# BMS_Enerdel_Adapter_rev8.net
KiCad netlist of a schematic drawn in EAGLE
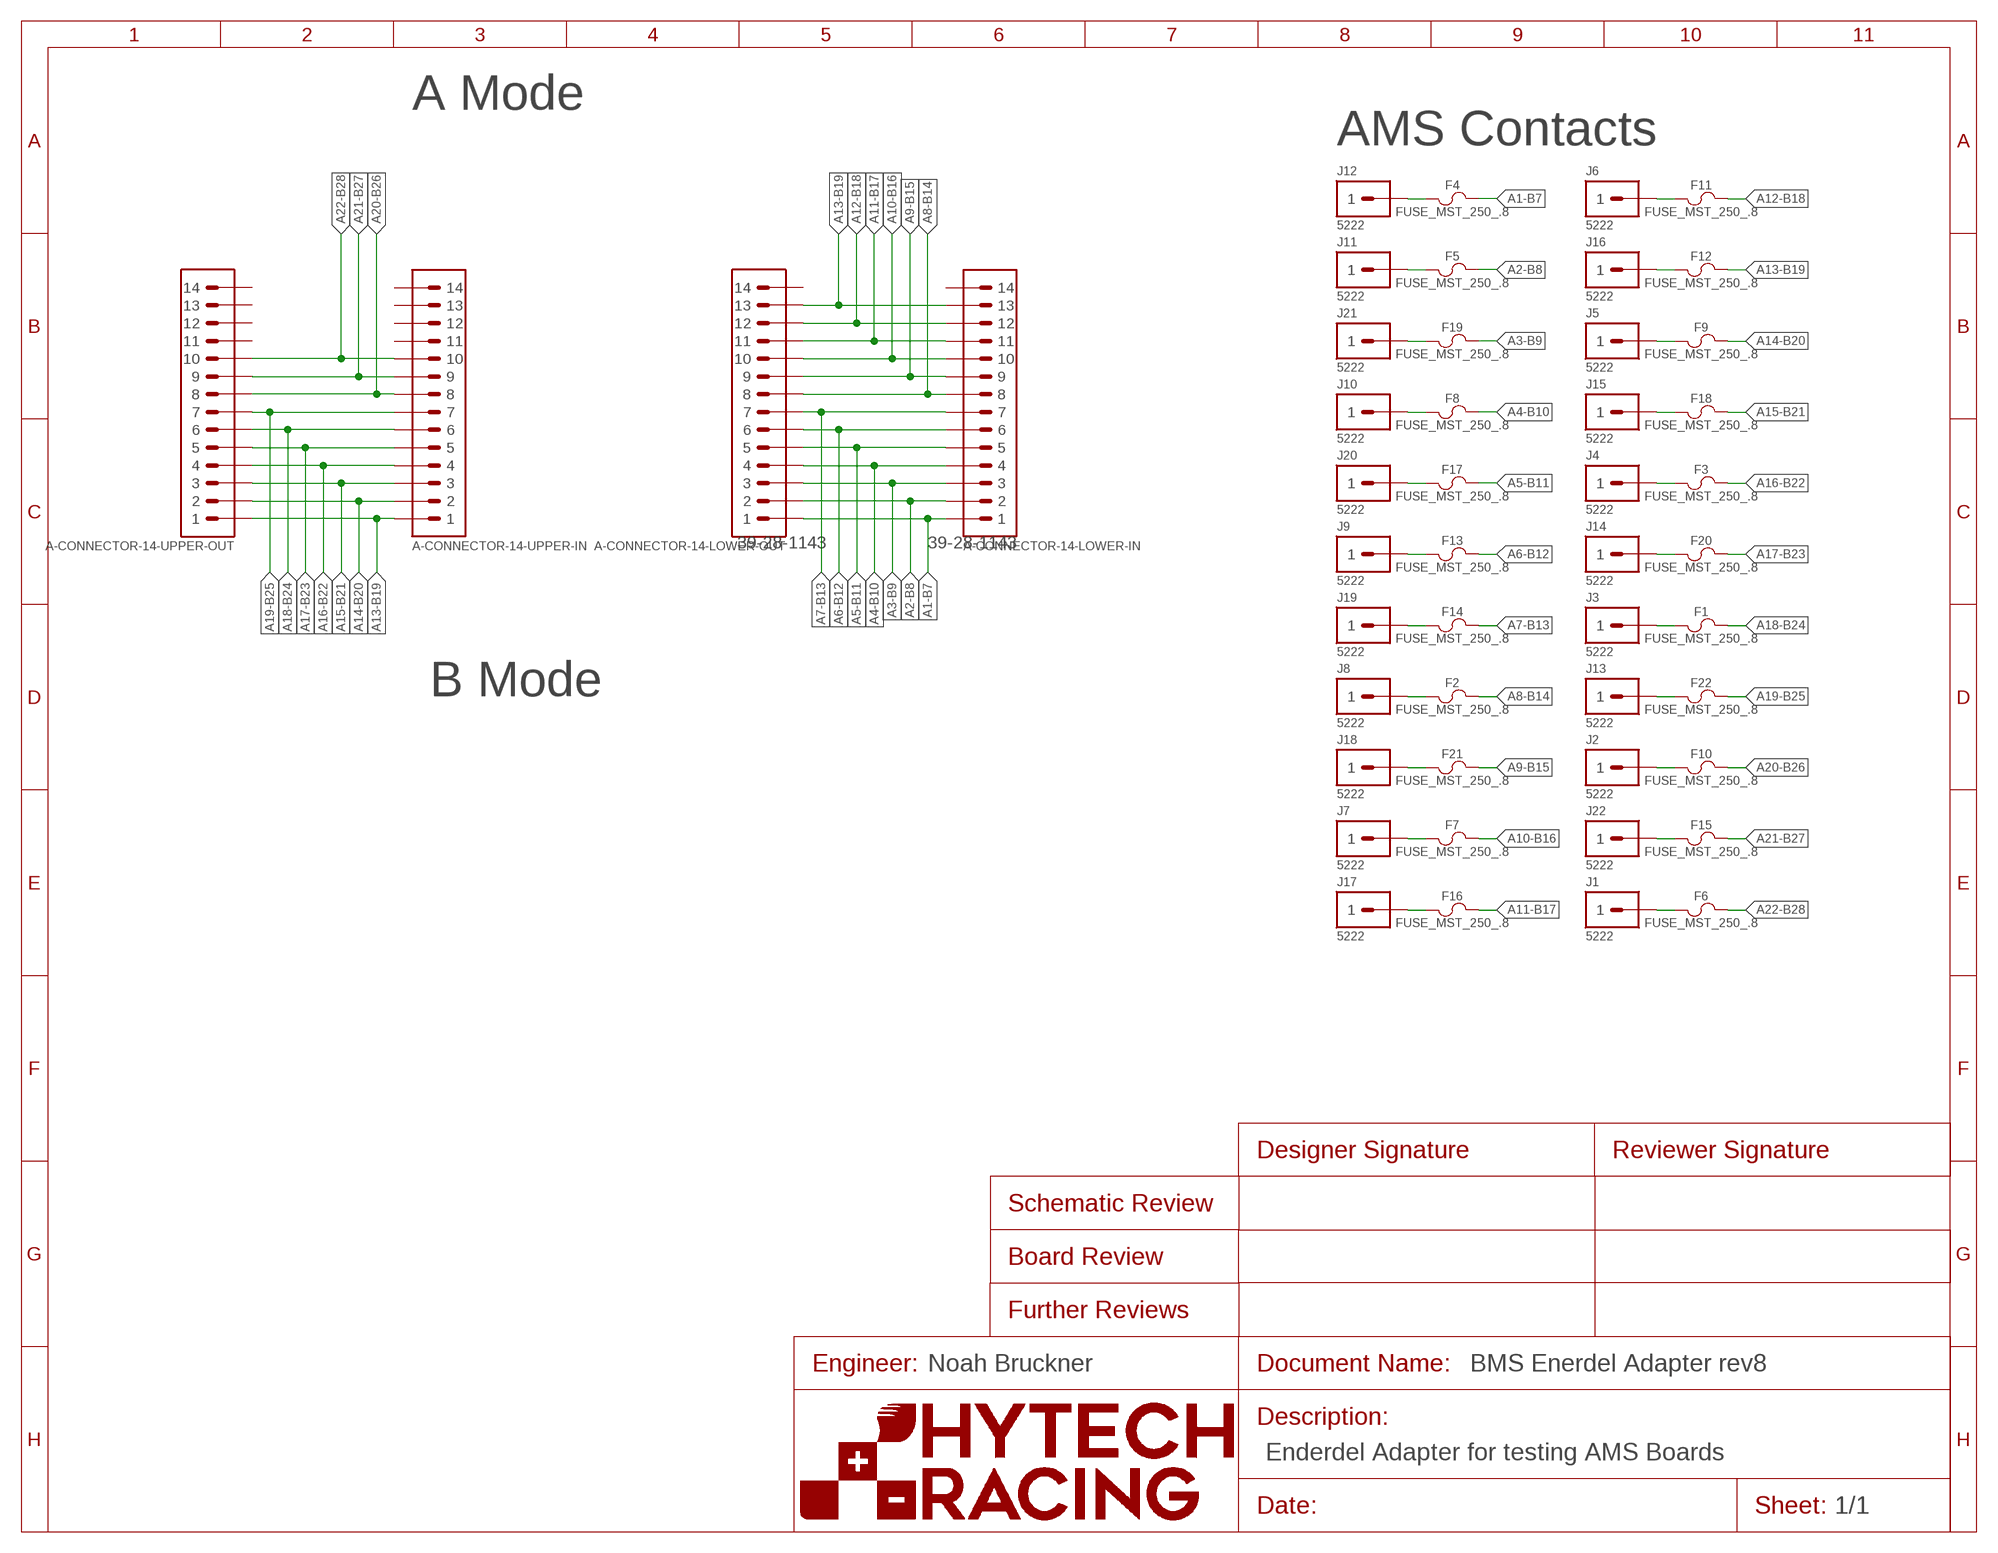
[diagram p0: schematic, sheet 1]

(export (version "E")
  (design (tool "Eeschema 10.0.6"))
  (components
    (comp (ref "A-CONNECTOR-14-LOWER-IN")
      (value "CONNECTOR-14_MINIFIT_")
      (footprint "eagle-import:MOLEX_MINIFIT_PTH_14")
      (fields (field (name "MPN") " 39-28-1143"))
      (libsource (lib "eagle-import") (part "CONNECTOR-14_?_MINIFIT"))
    )
    (comp (ref "A-CONNECTOR-14-LOWER-OUT")
      (value "CONNECTOR-14_MINIFIT_")
      (footprint "eagle-import:MOLEX_MINIFIT_PTH_14")
      (fields (field (name "MPN") " 39-28-1143"))
      (libsource (lib "eagle-import") (part "CONNECTOR-14_?_MINIFIT"))
    )
    (comp (ref "A-CONNECTOR-14-UPPER-IN")
      (value "CONNECTOR-14_NANOFIT_")
      (footprint "eagle-import:MOLEX_NANOFIT_PTH_14")
      (libsource (lib "eagle-import") (part "CONNECTOR-14_?_NANOFIT"))
    )
    (comp (ref "A-CONNECTOR-14-UPPER-OUT")
      (value "CONNECTOR-14_NANOFIT_")
      (footprint "eagle-import:MOLEX_NANOFIT_PTH_14")
      (libsource (lib "eagle-import") (part "CONNECTOR-14_?_NANOFIT"))
    )
    (comp (ref "F1")
      (value "FUSE_MST_250_.8")
      (footprint "eagle-import:MST_250")
      (fields
        (field (name "MANUFACTURER") "Schurter Inc.")
        (field (name "MPN") "0034.6614")
        (field (name "VOLTAGE") "63V")
      )
      (libsource (lib "eagle-import") (part "FUSE_?_MST_250.8"))
    )
    (comp (ref "F2")
      (value "FUSE_MST_250_.8")
      (footprint "eagle-import:MST_250")
      (fields
        (field (name "MANUFACTURER") "Schurter Inc.")
        (field (name "MPN") "0034.6614")
        (field (name "VOLTAGE") "63V")
      )
      (libsource (lib "eagle-import") (part "FUSE_?_MST_250.8"))
    )
    (comp (ref "F3")
      (value "FUSE_MST_250_.8")
      (footprint "eagle-import:MST_250")
      (fields
        (field (name "MANUFACTURER") "Schurter Inc.")
        (field (name "MPN") "0034.6614")
        (field (name "VOLTAGE") "63V")
      )
      (libsource (lib "eagle-import") (part "FUSE_?_MST_250.8"))
    )
    (comp (ref "F4")
      (value "FUSE_MST_250_.8")
      (footprint "eagle-import:MST_250")
      (fields
        (field (name "MANUFACTURER") "Schurter Inc.")
        (field (name "MPN") "0034.6614")
        (field (name "VOLTAGE") "63V")
      )
      (libsource (lib "eagle-import") (part "FUSE_?_MST_250.8"))
    )
    (comp (ref "F5")
      (value "FUSE_MST_250_.8")
      (footprint "eagle-import:MST_250")
      (fields
        (field (name "MANUFACTURER") "Schurter Inc.")
        (field (name "MPN") "0034.6614")
        (field (name "VOLTAGE") "63V")
      )
      (libsource (lib "eagle-import") (part "FUSE_?_MST_250.8"))
    )
    (comp (ref "F6")
      (value "FUSE_MST_250_.8")
      (footprint "eagle-import:MST_250")
      (fields
        (field (name "MANUFACTURER") "Schurter Inc.")
        (field (name "MPN") "0034.6614")
        (field (name "VOLTAGE") "63V")
      )
      (libsource (lib "eagle-import") (part "FUSE_?_MST_250.8"))
    )
    (comp (ref "F7")
      (value "FUSE_MST_250_.8")
      (footprint "eagle-import:MST_250")
      (fields
        (field (name "MANUFACTURER") "Schurter Inc.")
        (field (name "MPN") "0034.6614")
        (field (name "VOLTAGE") "63V")
      )
      (libsource (lib "eagle-import") (part "FUSE_?_MST_250.8"))
    )
    (comp (ref "F8")
      (value "FUSE_MST_250_.8")
      (footprint "eagle-import:MST_250")
      (fields
        (field (name "MANUFACTURER") "Schurter Inc.")
        (field (name "MPN") "0034.6614")
        (field (name "VOLTAGE") "63V")
      )
      (libsource (lib "eagle-import") (part "FUSE_?_MST_250.8"))
    )
    (comp (ref "F9")
      (value "FUSE_MST_250_.8")
      (footprint "eagle-import:MST_250")
      (fields
        (field (name "MANUFACTURER") "Schurter Inc.")
        (field (name "MPN") "0034.6614")
        (field (name "VOLTAGE") "63V")
      )
      (libsource (lib "eagle-import") (part "FUSE_?_MST_250.8"))
    )
    (comp (ref "F10")
      (value "FUSE_MST_250_.8")
      (footprint "eagle-import:MST_250")
      (fields
        (field (name "MANUFACTURER") "Schurter Inc.")
        (field (name "MPN") "0034.6614")
        (field (name "VOLTAGE") "63V")
      )
      (libsource (lib "eagle-import") (part "FUSE_?_MST_250.8"))
    )
    (comp (ref "F11")
      (value "FUSE_MST_250_.8")
      (footprint "eagle-import:MST_250")
      (fields
        (field (name "MANUFACTURER") "Schurter Inc.")
        (field (name "MPN") "0034.6614")
        (field (name "VOLTAGE") "63V")
      )
      (libsource (lib "eagle-import") (part "FUSE_?_MST_250.8"))
    )
    (comp (ref "F12")
      (value "FUSE_MST_250_.8")
      (footprint "eagle-import:MST_250")
      (fields
        (field (name "MANUFACTURER") "Schurter Inc.")
        (field (name "MPN") "0034.6614")
        (field (name "VOLTAGE") "63V")
      )
      (libsource (lib "eagle-import") (part "FUSE_?_MST_250.8"))
    )
    (comp (ref "F13")
      (value "FUSE_MST_250_.8")
      (footprint "eagle-import:MST_250")
      (fields
        (field (name "MANUFACTURER") "Schurter Inc.")
        (field (name "MPN") "0034.6614")
        (field (name "VOLTAGE") "63V")
      )
      (libsource (lib "eagle-import") (part "FUSE_?_MST_250.8"))
    )
    (comp (ref "F14")
      (value "FUSE_MST_250_.8")
      (footprint "eagle-import:MST_250")
      (fields
        (field (name "MANUFACTURER") "Schurter Inc.")
        (field (name "MPN") "0034.6614")
        (field (name "VOLTAGE") "63V")
      )
      (libsource (lib "eagle-import") (part "FUSE_?_MST_250.8"))
    )
    (comp (ref "F15")
      (value "FUSE_MST_250_.8")
      (footprint "eagle-import:MST_250")
      (fields
        (field (name "MANUFACTURER") "Schurter Inc.")
        (field (name "MPN") "0034.6614")
        (field (name "VOLTAGE") "63V")
      )
      (libsource (lib "eagle-import") (part "FUSE_?_MST_250.8"))
    )
    (comp (ref "F16")
      (value "FUSE_MST_250_.8")
      (footprint "eagle-import:MST_250")
      (fields
        (field (name "MANUFACTURER") "Schurter Inc.")
        (field (name "MPN") "0034.6614")
        (field (name "VOLTAGE") "63V")
      )
      (libsource (lib "eagle-import") (part "FUSE_?_MST_250.8"))
    )
    (comp (ref "F17")
      (value "FUSE_MST_250_.8")
      (footprint "eagle-import:MST_250")
      (fields
        (field (name "MANUFACTURER") "Schurter Inc.")
        (field (name "MPN") "0034.6614")
        (field (name "VOLTAGE") "63V")
      )
      (libsource (lib "eagle-import") (part "FUSE_?_MST_250.8"))
    )
    (comp (ref "F18")
      (value "FUSE_MST_250_.8")
      (footprint "eagle-import:MST_250")
      (fields
        (field (name "MANUFACTURER") "Schurter Inc.")
        (field (name "MPN") "0034.6614")
        (field (name "VOLTAGE") "63V")
      )
      (libsource (lib "eagle-import") (part "FUSE_?_MST_250.8"))
    )
    (comp (ref "F19")
      (value "FUSE_MST_250_.8")
      (footprint "eagle-import:MST_250")
      (fields
        (field (name "MANUFACTURER") "Schurter Inc.")
        (field (name "MPN") "0034.6614")
        (field (name "VOLTAGE") "63V")
      )
      (libsource (lib "eagle-import") (part "FUSE_?_MST_250.8"))
    )
    (comp (ref "F20")
      (value "FUSE_MST_250_.8")
      (footprint "eagle-import:MST_250")
      (fields
        (field (name "MANUFACTURER") "Schurter Inc.")
        (field (name "MPN") "0034.6614")
        (field (name "VOLTAGE") "63V")
      )
      (libsource (lib "eagle-import") (part "FUSE_?_MST_250.8"))
    )
    (comp (ref "F21")
      (value "FUSE_MST_250_.8")
      (footprint "eagle-import:MST_250")
      (fields
        (field (name "MANUFACTURER") "Schurter Inc.")
        (field (name "MPN") "0034.6614")
        (field (name "VOLTAGE") "63V")
      )
      (libsource (lib "eagle-import") (part "FUSE_?_MST_250.8"))
    )
    (comp (ref "F22")
      (value "FUSE_MST_250_.8")
      (footprint "eagle-import:MST_250")
      (fields
        (field (name "MANUFACTURER") "Schurter Inc.")
        (field (name "MPN") "0034.6614")
        (field (name "VOLTAGE") "63V")
      )
      (libsource (lib "eagle-import") (part "FUSE_?_MST_250.8"))
    )
    (comp (ref "J1")
      (value "CONNECTOR-1_5222_")
      (footprint "eagle-import:5222")
      (fields (field (name "MPN") "5222") (field (name "MANUFACTURER") "Keystone Electronics"))
      (libsource (lib "eagle-import") (part "CONNECTOR-1_?_5222"))
    )
    (comp (ref "J2")
      (value "CONNECTOR-1_5222_")
      (footprint "eagle-import:5222")
      (fields (field (name "MPN") "5222") (field (name "MANUFACTURER") "Keystone Electronics"))
      (libsource (lib "eagle-import") (part "CONNECTOR-1_?_5222"))
    )
    (comp (ref "J3")
      (value "CONNECTOR-1_5222_")
      (footprint "eagle-import:5222")
      (fields (field (name "MPN") "5222") (field (name "MANUFACTURER") "Keystone Electronics"))
      (libsource (lib "eagle-import") (part "CONNECTOR-1_?_5222"))
    )
    (comp (ref "J4")
      (value "CONNECTOR-1_5222_")
      (footprint "eagle-import:5222")
      (fields (field (name "MPN") "5222") (field (name "MANUFACTURER") "Keystone Electronics"))
      (libsource (lib "eagle-import") (part "CONNECTOR-1_?_5222"))
    )
    (comp (ref "J5")
      (value "CONNECTOR-1_5222_")
      (footprint "eagle-import:5222")
      (fields (field (name "MPN") "5222") (field (name "MANUFACTURER") "Keystone Electronics"))
      (libsource (lib "eagle-import") (part "CONNECTOR-1_?_5222"))
    )
    (comp (ref "J6")
      (value "CONNECTOR-1_5222_")
      (footprint "eagle-import:5222")
      (fields (field (name "MPN") "5222") (field (name "MANUFACTURER") "Keystone Electronics"))
      (libsource (lib "eagle-import") (part "CONNECTOR-1_?_5222"))
    )
    (comp (ref "J7")
      (value "CONNECTOR-1_5222_")
      (footprint "eagle-import:5222")
      (fields (field (name "MPN") "5222") (field (name "MANUFACTURER") "Keystone Electronics"))
      (libsource (lib "eagle-import") (part "CONNECTOR-1_?_5222"))
    )
    (comp (ref "J8")
      (value "CONNECTOR-1_5222_")
      (footprint "eagle-import:5222")
      (fields (field (name "MPN") "5222") (field (name "MANUFACTURER") "Keystone Electronics"))
      (libsource (lib "eagle-import") (part "CONNECTOR-1_?_5222"))
    )
    (comp (ref "J9")
      (value "CONNECTOR-1_5222_")
      (footprint "eagle-import:5222")
      (fields (field (name "MPN") "5222") (field (name "MANUFACTURER") "Keystone Electronics"))
      (libsource (lib "eagle-import") (part "CONNECTOR-1_?_5222"))
    )
    (comp (ref "J10")
      (value "CONNECTOR-1_5222_")
      (footprint "eagle-import:5222")
      (fields (field (name "MPN") "5222") (field (name "MANUFACTURER") "Keystone Electronics"))
      (libsource (lib "eagle-import") (part "CONNECTOR-1_?_5222"))
    )
    (comp (ref "J11")
      (value "CONNECTOR-1_5222_")
      (footprint "eagle-import:5222")
      (fields (field (name "MPN") "5222") (field (name "MANUFACTURER") "Keystone Electronics"))
      (libsource (lib "eagle-import") (part "CONNECTOR-1_?_5222"))
    )
    (comp (ref "J12")
      (value "CONNECTOR-1_5222_")
      (footprint "eagle-import:5222")
      (fields (field (name "MPN") "5222") (field (name "MANUFACTURER") "Keystone Electronics"))
      (libsource (lib "eagle-import") (part "CONNECTOR-1_?_5222"))
    )
    (comp (ref "J13")
      (value "CONNECTOR-1_5222_")
      (footprint "eagle-import:5222")
      (fields (field (name "MPN") "5222") (field (name "MANUFACTURER") "Keystone Electronics"))
      (libsource (lib "eagle-import") (part "CONNECTOR-1_?_5222"))
    )
    (comp (ref "J14")
      (value "CONNECTOR-1_5222_")
      (footprint "eagle-import:5222")
      (fields (field (name "MPN") "5222") (field (name "MANUFACTURER") "Keystone Electronics"))
      (libsource (lib "eagle-import") (part "CONNECTOR-1_?_5222"))
    )
    (comp (ref "J15")
      (value "CONNECTOR-1_5222_")
      (footprint "eagle-import:5222")
      (fields (field (name "MPN") "5222") (field (name "MANUFACTURER") "Keystone Electronics"))
      (libsource (lib "eagle-import") (part "CONNECTOR-1_?_5222"))
    )
    (comp (ref "J16")
      (value "CONNECTOR-1_5222_")
      (footprint "eagle-import:5222")
      (fields (field (name "MPN") "5222") (field (name "MANUFACTURER") "Keystone Electronics"))
      (libsource (lib "eagle-import") (part "CONNECTOR-1_?_5222"))
    )
    (comp (ref "J17")
      (value "CONNECTOR-1_5222_")
      (footprint "eagle-import:5222")
      (fields (field (name "MPN") "5222") (field (name "MANUFACTURER") "Keystone Electronics"))
      (libsource (lib "eagle-import") (part "CONNECTOR-1_?_5222"))
    )
    (comp (ref "J18")
      (value "CONNECTOR-1_5222_")
      (footprint "eagle-import:5222")
      (fields (field (name "MPN") "5222") (field (name "MANUFACTURER") "Keystone Electronics"))
      (libsource (lib "eagle-import") (part "CONNECTOR-1_?_5222"))
    )
    (comp (ref "J19")
      (value "CONNECTOR-1_5222_")
      (footprint "eagle-import:5222")
      (fields (field (name "MPN") "5222") (field (name "MANUFACTURER") "Keystone Electronics"))
      (libsource (lib "eagle-import") (part "CONNECTOR-1_?_5222"))
    )
    (comp (ref "J20")
      (value "CONNECTOR-1_5222_")
      (footprint "eagle-import:5222")
      (fields (field (name "MPN") "5222") (field (name "MANUFACTURER") "Keystone Electronics"))
      (libsource (lib "eagle-import") (part "CONNECTOR-1_?_5222"))
    )
    (comp (ref "J21")
      (value "CONNECTOR-1_5222_")
      (footprint "eagle-import:5222")
      (fields (field (name "MPN") "5222") (field (name "MANUFACTURER") "Keystone Electronics"))
      (libsource (lib "eagle-import") (part "CONNECTOR-1_?_5222"))
    )
    (comp (ref "J22")
      (value "CONNECTOR-1_5222_")
      (footprint "eagle-import:5222")
      (fields (field (name "MPN") "5222") (field (name "MANUFACTURER") "Keystone Electronics"))
      (libsource (lib "eagle-import") (part "CONNECTOR-1_?_5222"))
    )
  )
  (nets
    (net (code "1") (name "A1-B7") (class "Default")
      (node (ref "A-CONNECTOR-14-LOWER-IN") (pin "1") (pinfunction "1_1") (pintype "passive"))
      (node (ref "A-CONNECTOR-14-LOWER-OUT") (pin "1") (pinfunction "1_1") (pintype "passive"))
      (node (ref "F4") (pin "2") (pinfunction "2_2") (pintype "passive"))
    )
    (net (code "2") (name "A2-B8") (class "Default")
      (node (ref "A-CONNECTOR-14-LOWER-IN") (pin "2") (pinfunction "2_2") (pintype "passive"))
      (node (ref "A-CONNECTOR-14-LOWER-OUT") (pin "2") (pinfunction "2_2") (pintype "passive"))
      (node (ref "F5") (pin "2") (pinfunction "2_2") (pintype "passive"))
    )
    (net (code "3") (name "A3-B9") (class "Default")
      (node (ref "A-CONNECTOR-14-LOWER-IN") (pin "3") (pinfunction "3_3") (pintype "passive"))
      (node (ref "A-CONNECTOR-14-LOWER-OUT") (pin "3") (pinfunction "3_3") (pintype "passive"))
      (node (ref "F19") (pin "2") (pinfunction "2_2") (pintype "passive"))
    )
    (net (code "4") (name "A4-B10") (class "Default")
      (node (ref "A-CONNECTOR-14-LOWER-IN") (pin "4") (pinfunction "4_4") (pintype "passive"))
      (node (ref "A-CONNECTOR-14-LOWER-OUT") (pin "4") (pinfunction "4_4") (pintype "passive"))
      (node (ref "F8") (pin "2") (pinfunction "2_2") (pintype "passive"))
    )
    (net (code "5") (name "A5-B11") (class "Default")
      (node (ref "A-CONNECTOR-14-LOWER-IN") (pin "5") (pinfunction "5_5") (pintype "passive"))
      (node (ref "A-CONNECTOR-14-LOWER-OUT") (pin "5") (pinfunction "5_5") (pintype "passive"))
      (node (ref "F17") (pin "2") (pinfunction "2_2") (pintype "passive"))
    )
    (net (code "6") (name "A6-B12") (class "Default")
      (node (ref "A-CONNECTOR-14-LOWER-IN") (pin "6") (pinfunction "6_6") (pintype "passive"))
      (node (ref "A-CONNECTOR-14-LOWER-OUT") (pin "6") (pinfunction "6_6") (pintype "passive"))
      (node (ref "F13") (pin "2") (pinfunction "2_2") (pintype "passive"))
    )
    (net (code "7") (name "A7-B13") (class "Default")
      (node (ref "A-CONNECTOR-14-LOWER-IN") (pin "7") (pinfunction "7_7") (pintype "passive"))
      (node (ref "A-CONNECTOR-14-LOWER-OUT") (pin "7") (pinfunction "7_7") (pintype "passive"))
      (node (ref "F14") (pin "2") (pinfunction "2_2") (pintype "passive"))
    )
    (net (code "8") (name "A8-B14") (class "Default")
      (node (ref "A-CONNECTOR-14-LOWER-IN") (pin "8") (pinfunction "8_8") (pintype "passive"))
      (node (ref "A-CONNECTOR-14-LOWER-OUT") (pin "8") (pinfunction "8_8") (pintype "passive"))
      (node (ref "F2") (pin "2") (pinfunction "2_2") (pintype "passive"))
    )
    (net (code "9") (name "A9-B15") (class "Default")
      (node (ref "A-CONNECTOR-14-LOWER-IN") (pin "9") (pinfunction "9_9") (pintype "passive"))
      (node (ref "A-CONNECTOR-14-LOWER-OUT") (pin "9") (pinfunction "9_9") (pintype "passive"))
      (node (ref "F21") (pin "2") (pinfunction "2_2") (pintype "passive"))
    )
    (net (code "10") (name "A10-B16") (class "Default")
      (node (ref "A-CONNECTOR-14-LOWER-IN") (pin "10") (pinfunction "10_10") (pintype "passive"))
      (node (ref "A-CONNECTOR-14-LOWER-OUT") (pin "10") (pinfunction "10_10") (pintype "passive"))
      (node (ref "F7") (pin "2") (pinfunction "2_2") (pintype "passive"))
    )
    (net (code "11") (name "A11-B17") (class "Default")
      (node (ref "A-CONNECTOR-14-LOWER-IN") (pin "11") (pinfunction "11_11") (pintype "passive"))
      (node (ref "A-CONNECTOR-14-LOWER-OUT") (pin "11") (pinfunction "11_11") (pintype "passive"))
      (node (ref "F16") (pin "2") (pinfunction "2_2") (pintype "passive"))
    )
    (net (code "12") (name "A12-B18") (class "Default")
      (node (ref "A-CONNECTOR-14-LOWER-IN") (pin "12") (pinfunction "12_12") (pintype "passive"))
      (node (ref "A-CONNECTOR-14-LOWER-OUT") (pin "12") (pinfunction "12_12") (pintype "passive"))
      (node (ref "F11") (pin "2") (pinfunction "2_2") (pintype "passive"))
    )
    (net (code "13") (name "A13-B19") (class "Default")
      (node (ref "A-CONNECTOR-14-LOWER-IN") (pin "13") (pinfunction "13_13") (pintype "passive"))
      (node (ref "A-CONNECTOR-14-LOWER-OUT") (pin "13") (pinfunction "13_13") (pintype "passive"))
      (node (ref "A-CONNECTOR-14-UPPER-IN") (pin "1") (pinfunction "1_1") (pintype "passive"))
      (node (ref "A-CONNECTOR-14-UPPER-OUT") (pin "1") (pinfunction "1_1") (pintype "passive"))
      (node (ref "F12") (pin "2") (pinfunction "2_2") (pintype "passive"))
    )
    (net (code "14") (name "A14-B20") (class "Default")
      (node (ref "A-CONNECTOR-14-UPPER-IN") (pin "2") (pinfunction "2_2") (pintype "passive"))
      (node (ref "A-CONNECTOR-14-UPPER-OUT") (pin "2") (pinfunction "2_2") (pintype "passive"))
      (node (ref "F9") (pin "2") (pinfunction "2_2") (pintype "passive"))
    )
    (net (code "15") (name "A15-B21") (class "Default")
      (node (ref "A-CONNECTOR-14-UPPER-IN") (pin "3") (pinfunction "3_3") (pintype "passive"))
      (node (ref "A-CONNECTOR-14-UPPER-OUT") (pin "3") (pinfunction "3_3") (pintype "passive"))
      (node (ref "F18") (pin "2") (pinfunction "2_2") (pintype "passive"))
    )
    (net (code "16") (name "A16-B22") (class "Default")
      (node (ref "A-CONNECTOR-14-UPPER-IN") (pin "4") (pinfunction "4_4") (pintype "passive"))
      (node (ref "A-CONNECTOR-14-UPPER-OUT") (pin "4") (pinfunction "4_4") (pintype "passive"))
      (node (ref "F3") (pin "2") (pinfunction "2_2") (pintype "passive"))
    )
    (net (code "17") (name "A17-B23") (class "Default")
      (node (ref "A-CONNECTOR-14-UPPER-IN") (pin "5") (pinfunction "5_5") (pintype "passive"))
      (node (ref "A-CONNECTOR-14-UPPER-OUT") (pin "5") (pinfunction "5_5") (pintype "passive"))
      (node (ref "F20") (pin "2") (pinfunction "2_2") (pintype "passive"))
    )
    (net (code "18") (name "A18-B24") (class "Default")
      (node (ref "A-CONNECTOR-14-UPPER-IN") (pin "6") (pinfunction "6_6") (pintype "passive"))
      (node (ref "A-CONNECTOR-14-UPPER-OUT") (pin "6") (pinfunction "6_6") (pintype "passive"))
      (node (ref "F1") (pin "2") (pinfunction "2_2") (pintype "passive"))
    )
    (net (code "19") (name "A19-B25") (class "Default")
      (node (ref "A-CONNECTOR-14-UPPER-IN") (pin "7") (pinfunction "7_7") (pintype "passive"))
      (node (ref "A-CONNECTOR-14-UPPER-OUT") (pin "7") (pinfunction "7_7") (pintype "passive"))
      (node (ref "F22") (pin "2") (pinfunction "2_2") (pintype "passive"))
    )
    (net (code "20") (name "A20-B26") (class "Default")
      (node (ref "A-CONNECTOR-14-UPPER-IN") (pin "8") (pinfunction "8_8") (pintype "passive"))
      (node (ref "A-CONNECTOR-14-UPPER-OUT") (pin "8") (pinfunction "8_8") (pintype "passive"))
      (node (ref "F10") (pin "2") (pinfunction "2_2") (pintype "passive"))
    )
    (net (code "21") (name "A21-B27") (class "Default")
      (node (ref "A-CONNECTOR-14-UPPER-IN") (pin "9") (pinfunction "9_9") (pintype "passive"))
      (node (ref "A-CONNECTOR-14-UPPER-OUT") (pin "9") (pinfunction "9_9") (pintype "passive"))
      (node (ref "F15") (pin "2") (pinfunction "2_2") (pintype "passive"))
    )
    (net (code "22") (name "A22-B28") (class "Default")
      (node (ref "A-CONNECTOR-14-UPPER-IN") (pin "10") (pinfunction "10_10") (pintype "passive"))
      (node (ref "A-CONNECTOR-14-UPPER-OUT") (pin "10") (pinfunction "10_10") (pintype "passive"))
      (node (ref "F6") (pin "2") (pinfunction "2_2") (pintype "passive"))
    )
    (net (code "23") (name "Net-(F1-Pad1)") (class "Default")
      (node (ref "F1") (pin "1") (pinfunction "1_1") (pintype "passive"))
      (node (ref "J3") (pin "1") (pinfunction "1_1") (pintype "passive"))
    )
    (net (code "24") (name "Net-(F2-Pad1)") (class "Default")
      (node (ref "F2") (pin "1") (pinfunction "1_1") (pintype "passive"))
      (node (ref "J8") (pin "1") (pinfunction "1_1") (pintype "passive"))
    )
    (net (code "25") (name "Net-(F3-Pad1)") (class "Default")
      (node (ref "F3") (pin "1") (pinfunction "1_1") (pintype "passive"))
      (node (ref "J4") (pin "1") (pinfunction "1_1") (pintype "passive"))
    )
    (net (code "26") (name "Net-(F4-Pad1)") (class "Default")
      (node (ref "F4") (pin "1") (pinfunction "1_1") (pintype "passive"))
      (node (ref "J12") (pin "1") (pinfunction "1_1") (pintype "passive"))
    )
    (net (code "27") (name "Net-(F5-Pad1)") (class "Default")
      (node (ref "F5") (pin "1") (pinfunction "1_1") (pintype "passive"))
      (node (ref "J11") (pin "1") (pinfunction "1_1") (pintype "passive"))
    )
    (net (code "28") (name "Net-(F6-Pad1)") (class "Default")
      (node (ref "F6") (pin "1") (pinfunction "1_1") (pintype "passive"))
      (node (ref "J1") (pin "1") (pinfunction "1_1") (pintype "passive"))
    )
    (net (code "29") (name "Net-(F7-Pad1)") (class "Default")
      (node (ref "F7") (pin "1") (pinfunction "1_1") (pintype "passive"))
      (node (ref "J7") (pin "1") (pinfunction "1_1") (pintype "passive"))
    )
    (net (code "30") (name "Net-(F8-Pad1)") (class "Default")
      (node (ref "F8") (pin "1") (pinfunction "1_1") (pintype "passive"))
      (node (ref "J10") (pin "1") (pinfunction "1_1") (pintype "passive"))
    )
    (net (code "31") (name "Net-(F9-Pad1)") (class "Default")
      (node (ref "F9") (pin "1") (pinfunction "1_1") (pintype "passive"))
      (node (ref "J5") (pin "1") (pinfunction "1_1") (pintype "passive"))
    )
    (net (code "32") (name "Net-(F10-Pad1)") (class "Default")
      (node (ref "F10") (pin "1") (pinfunction "1_1") (pintype "passive"))
      (node (ref "J2") (pin "1") (pinfunction "1_1") (pintype "passive"))
    )
    (net (code "33") (name "Net-(F11-Pad1)") (class "Default")
      (node (ref "F11") (pin "1") (pinfunction "1_1") (pintype "passive"))
      (node (ref "J6") (pin "1") (pinfunction "1_1") (pintype "passive"))
    )
    (net (code "34") (name "Net-(F12-Pad1)") (class "Default")
      (node (ref "F12") (pin "1") (pinfunction "1_1") (pintype "passive"))
      (node (ref "J16") (pin "1") (pinfunction "1_1") (pintype "passive"))
    )
    (net (code "35") (name "Net-(F13-Pad1)") (class "Default")
      (node (ref "F13") (pin "1") (pinfunction "1_1") (pintype "passive"))
      (node (ref "J9") (pin "1") (pinfunction "1_1") (pintype "passive"))
    )
    (net (code "36") (name "Net-(F14-Pad1)") (class "Default")
      (node (ref "F14") (pin "1") (pinfunction "1_1") (pintype "passive"))
      (node (ref "J19") (pin "1") (pinfunction "1_1") (pintype "passive"))
    )
    (net (code "37") (name "Net-(F15-Pad1)") (class "Default")
      (node (ref "F15") (pin "1") (pinfunction "1_1") (pintype "passive"))
      (node (ref "J22") (pin "1") (pinfunction "1_1") (pintype "passive"))
    )
    (net (code "38") (name "Net-(F16-Pad1)") (class "Default")
      (node (ref "F16") (pin "1") (pinfunction "1_1") (pintype "passive"))
      (node (ref "J17") (pin "1") (pinfunction "1_1") (pintype "passive"))
    )
    (net (code "39") (name "Net-(F17-Pad1)") (class "Default")
      (node (ref "F17") (pin "1") (pinfunction "1_1") (pintype "passive"))
      (node (ref "J20") (pin "1") (pinfunction "1_1") (pintype "passive"))
    )
    (net (code "40") (name "Net-(F18-Pad1)") (class "Default")
      (node (ref "F18") (pin "1") (pinfunction "1_1") (pintype "passive"))
      (node (ref "J15") (pin "1") (pinfunction "1_1") (pintype "passive"))
    )
    (net (code "41") (name "Net-(F19-Pad1)") (class "Default")
      (node (ref "F19") (pin "1") (pinfunction "1_1") (pintype "passive"))
      (node (ref "J21") (pin "1") (pinfunction "1_1") (pintype "passive"))
    )
    (net (code "42") (name "Net-(F20-Pad1)") (class "Default")
      (node (ref "F20") (pin "1") (pinfunction "1_1") (pintype "passive"))
      (node (ref "J14") (pin "1") (pinfunction "1_1") (pintype "passive"))
    )
    (net (code "43") (name "Net-(F21-Pad1)") (class "Default")
      (node (ref "F21") (pin "1") (pinfunction "1_1") (pintype "passive"))
      (node (ref "J18") (pin "1") (pinfunction "1_1") (pintype "passive"))
    )
    (net (code "44") (name "Net-(F22-Pad1)") (class "Default")
      (node (ref "F22") (pin "1") (pinfunction "1_1") (pintype "passive"))
      (node (ref "J13") (pin "1") (pinfunction "1_1") (pintype "passive"))
    )
    (net (code "45") (name "unconnected-(A-CONNECTOR-14-LOWER-IN-Pad14)") (class "Default")
      (node (ref "A-CONNECTOR-14-LOWER-IN") (pin "14") (pinfunction "14_14") (pintype "passive"))
    )
    (net (code "46") (name "unconnected-(A-CONNECTOR-14-LOWER-OUT-Pad14)") (class "Default")
      (node (ref "A-CONNECTOR-14-LOWER-OUT") (pin "14") (pinfunction "14_14") (pintype "passive"))
    )
    (net (code "47") (name "unconnected-(A-CONNECTOR-14-UPPER-IN-Pad11)") (class "Default")
      (node (ref "A-CONNECTOR-14-UPPER-IN") (pin "11") (pinfunction "11_11") (pintype "passive"))
    )
    (net (code "48") (name "unconnected-(A-CONNECTOR-14-UPPER-IN-Pad12)") (class "Default")
      (node (ref "A-CONNECTOR-14-UPPER-IN") (pin "12") (pinfunction "12_12") (pintype "passive"))
    )
    (net (code "49") (name "unconnected-(A-CONNECTOR-14-UPPER-IN-Pad13)") (class "Default")
      (node (ref "A-CONNECTOR-14-UPPER-IN") (pin "13") (pinfunction "13_13") (pintype "passive"))
    )
    (net (code "50") (name "unconnected-(A-CONNECTOR-14-UPPER-IN-Pad14)") (class "Default")
      (node (ref "A-CONNECTOR-14-UPPER-IN") (pin "14") (pinfunction "14_14") (pintype "passive"))
    )
    (net (code "51") (name "unconnected-(A-CONNECTOR-14-UPPER-OUT-Pad11)") (class "Default")
      (node (ref "A-CONNECTOR-14-UPPER-OUT") (pin "11") (pinfunction "11_11") (pintype "passive"))
    )
    (net (code "52") (name "unconnected-(A-CONNECTOR-14-UPPER-OUT-Pad12)") (class "Default")
      (node (ref "A-CONNECTOR-14-UPPER-OUT") (pin "12") (pinfunction "12_12") (pintype "passive"))
    )
    (net (code "53") (name "unconnected-(A-CONNECTOR-14-UPPER-OUT-Pad13)") (class "Default")
      (node (ref "A-CONNECTOR-14-UPPER-OUT") (pin "13") (pinfunction "13_13") (pintype "passive"))
    )
    (net (code "54") (name "unconnected-(A-CONNECTOR-14-UPPER-OUT-Pad14)") (class "Default")
      (node (ref "A-CONNECTOR-14-UPPER-OUT") (pin "14") (pinfunction "14_14") (pintype "passive"))
    )
  )
)
